# OfflineFlyback_V1.net
KiCad netlist of a schematic drawn in Altium Designer
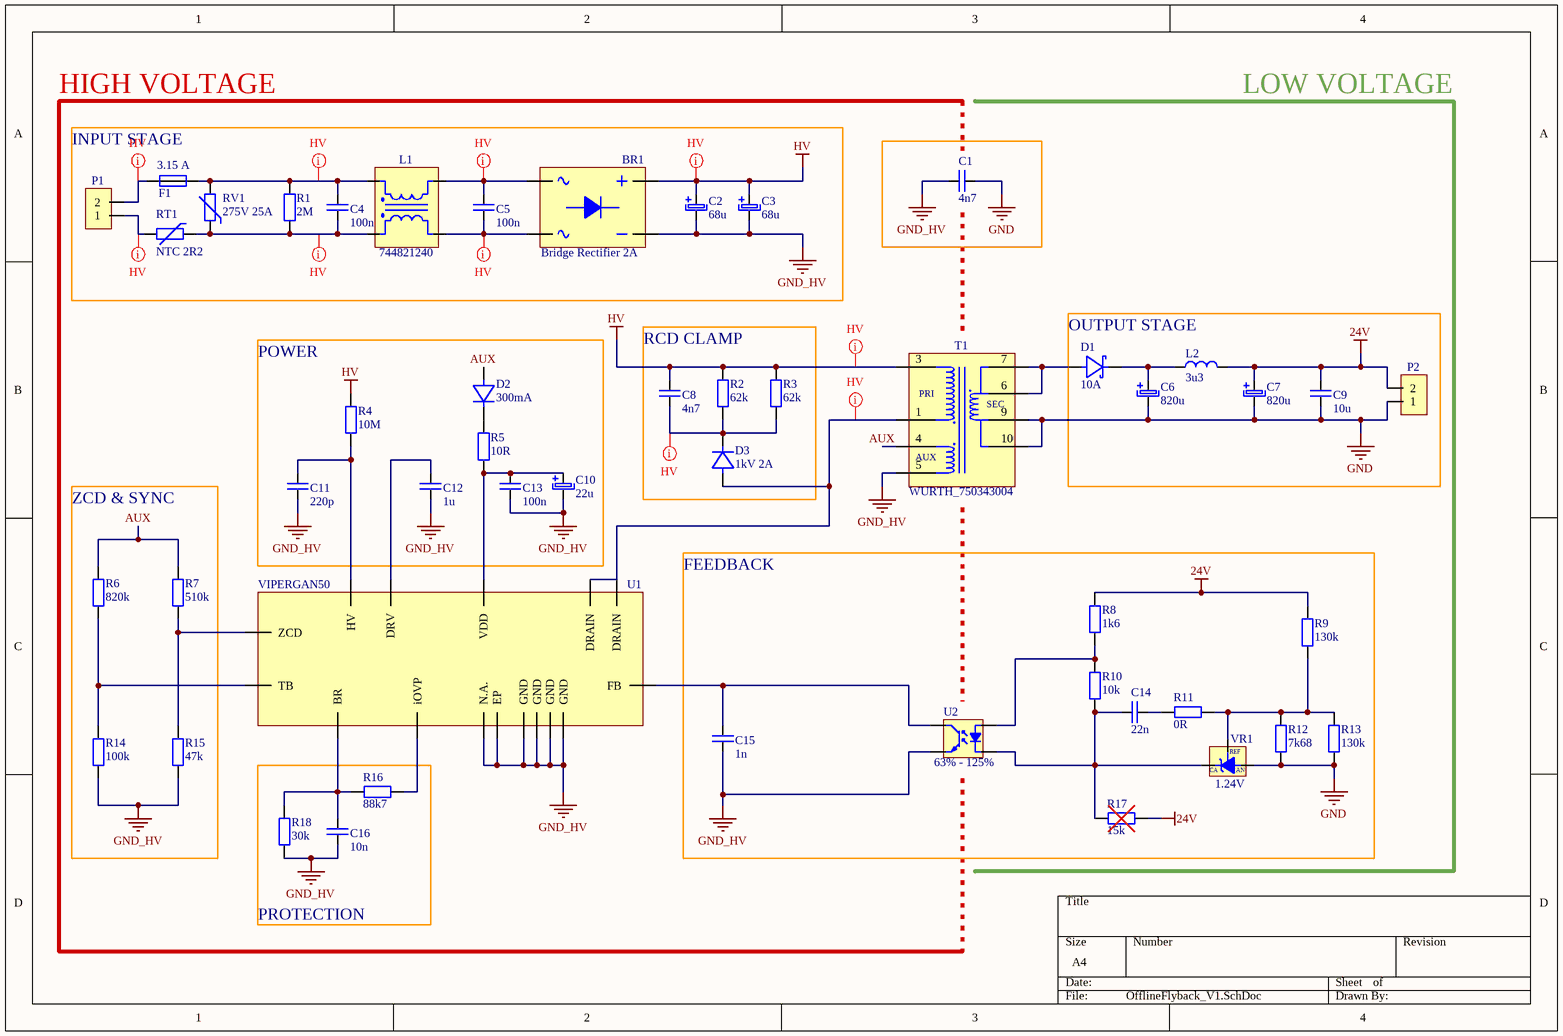
[diagram p0: OfflineFlyback_V1.SchDoc]

(export (version "E")
  (design (tool "Eeschema 10.0.6"))
  (components
    (comp (ref "BR1")
      (value "Bridge Rectifier 2A")
      (footprint "full_bridge_rectifier_SMD")
      (description "Bourns CD-MBL210SL")
      (libsource (lib "generic") (part "Bridge Rectifier"))
    )
    (comp (ref "C1")
      (value "4n7")
      (footprint "capacitor_tht_10mm_lead_2_slim")
      (description "TDK CD12ZU2GA472MYNKA Y1")
      (libsource (lib "generic") (part "Capacitor - non-polarised"))
    )
    (comp (ref "C2")
      (value "68u")
      (footprint "capacitor_tht_7mm5_lead_18mm")
      (description "Panasonic EEU-EE2G680")
      (libsource (lib "generic") (part "Capacitor - polarised"))
    )
    (comp (ref "C3")
      (value "68u")
      (footprint "capacitor_tht_7mm5_lead_18mm")
      (description "Panasonic EEU-EE2G680")
      (libsource (lib "generic") (part "Capacitor - polarised"))
    )
    (comp (ref "C4")
      (value "100n")
      (footprint "capacitor_tht_10mm_lead")
      (description "Vishay / BC Components BFC233920104 X2")
      (libsource (lib "generic") (part "Capacitor - non-polarised"))
    )
    (comp (ref "C5")
      (value "100n")
      (footprint "capacitor_tht_10mm_lead")
      (description "Vishay / BC Components BFC233920104 X2")
      (libsource (lib "generic") (part "Capacitor - non-polarised"))
    )
    (comp (ref "C6")
      (value "820u")
      (footprint "capacitor_tht_5mm_lead_10mm")
      (description "Panasonic EEU-FR1V821L")
      (libsource (lib "generic") (part "Capacitor - polarised"))
    )
    (comp (ref "C7")
      (value "820u")
      (footprint "capacitor_tht_5mm_lead_10mm")
      (description "Panasonic EEU-FR1V821L")
      (libsource (lib "generic") (part "Capacitor - polarised"))
    )
    (comp (ref "C8")
      (value "4n7")
      (footprint "capacitor_smd_1206")
      (description "Kyocera AVX 1206AC472KAT2A X7R")
      (libsource (lib "generic") (part "Capacitor - non-polarised"))
    )
    (comp (ref "C9")
      (value "10u")
      (footprint "capacitor_smd_1206")
      (description "Samsung CL31B106KBHNNNE X7R")
      (libsource (lib "generic") (part "Capacitor - non-polarised"))
    )
    (comp (ref "C10")
      (value "22u")
      (footprint "capacitor_tht_2mm5_lead_6mm3")
      (description "Wurth 860240673003")
      (libsource (lib "generic") (part "Capacitor - polarised"))
    )
    (comp (ref "C11")
      (value "220p")
      (footprint "capacitor_smd_0603")
      (description "Samsung CL10B221KC8WPNC X7R")
      (libsource (lib "generic") (part "Capacitor - non-polarised"))
    )
    (comp (ref "C12")
      (value "1u")
      (footprint "capacitor_smd_0603")
      (description "Samsung CL10B105KB9VPJC X7R")
      (libsource (lib "generic") (part "Capacitor - non-polarised"))
    )
    (comp (ref "C13")
      (value "100n")
      (footprint "capacitor_smd_0603")
      (description "Vishay / Vitramon GA0603Y104KXAAC31G X7R")
      (libsource (lib "generic") (part "Capacitor - non-polarised"))
    )
    (comp (ref "C14")
      (value "22n")
      (footprint "capacitor_smd_0603")
      (description "Kyocera AVX 06035C223K4T2A X7R")
      (libsource (lib "generic") (part "Capacitor - non-polarised"))
    )
    (comp (ref "C15")
      (value "1n")
      (footprint "capacitor_smd_0603")
      (description "Murata GRM1885C1H102JA01D C0G")
      (libsource (lib "generic") (part "Capacitor - non-polarised"))
    )
    (comp (ref "C16")
      (value "10n")
      (footprint "capacitor_smd_0603")
      (description "Murata GCM188R71H103KA37J X7R")
      (libsource (lib "generic") (part "Capacitor - non-polarised"))
    )
    (comp (ref "D1")
      (value "10A")
      (footprint "diode_TO_2787C")
      (description "Panjit MBR10H150PC-AU_R2_007A1")
      (libsource (lib "generic") (part "Diode - Schottkey"))
    )
    (comp (ref "D2")
      (value "300mA")
      (footprint "diode_smd_sod_123")
      (description "Vishay 1N4148W-HG3_A-08")
      (libsource (lib "generic") (part "Diode - silicon"))
    )
    (comp (ref "D3")
      (value "1kV 2A")
      (footprint "diode_smd_smb")
      (description "MCC FR2M-LTP")
      (libsource (lib "generic") (part "Diode - silicon"))
    )
    (comp (ref "F1")
      (value "3.15 A")
      (footprint "fuse_tht_5mm08")
      (description "Littelfuse 40013150440 3.15 A Slow Blow")
      (libsource (lib "generic") (part "Fuse"))
    )
    (comp (ref "L1")
      (value "744821240")
      (footprint "wurth_common_mode_choke_4mm5_10mm")
      (description "Wurth 744821240 1.5A 4mH")
      (libsource (lib "generic") (part "Common Mode Choke"))
    )
    (comp (ref "L2")
      (value "3u3")
      (footprint "inductor_smd_6mm6_x_7mm3")
      (description "Bourns SRP7028A-3R3M")
      (libsource (lib "generic") (part "Inductor"))
    )
    (comp (ref "P1")
      (value "Terminal Block")
      (footprint "terminal_block_1X2_5mm08")
      (description "Adam Tech EBAFA-02-D")
      (libsource (lib "") (part "Terminal Block 1X2_1"))
    )
    (comp (ref "P2")
      (value "Terminal Block")
      (footprint "terminal_block_1X2_5mm08")
      (description "Adam Tech EBAFA-02-D")
      (libsource (lib "terminal_blocks") (part "Terminal Block 1X2"))
    )
    (comp (ref "R1")
      (value "2M")
      (footprint "resisitor_smd_1206")
      (description "Vishay / Draloric RCV12062M00JNEA")
      (libsource (lib "generic") (part "Resistor"))
    )
    (comp (ref "R2")
      (value "62k")
      (footprint "resisitor_smd_1206")
      (description "Panasonic ERJ-UP8F6202V")
      (libsource (lib "generic") (part "Resistor"))
    )
    (comp (ref "R3")
      (value "62k")
      (footprint "resisitor_smd_1206")
      (description "Panasonic ERJ-UP8F6202V")
      (libsource (lib "generic") (part "Resistor"))
    )
    (comp (ref "R4")
      (value "10M")
      (footprint "resisitor_smd_1210")
      (description "ROHM KTR25JZPF1005")
      (libsource (lib "generic") (part "Resistor"))
    )
    (comp (ref "R5")
      (value "10R")
      (footprint "resisitor_smd_0603")
      (description "Vishay CRCW060310R0FKED")
      (libsource (lib "generic") (part "Resistor"))
    )
    (comp (ref "R6")
      (value "820k")
      (footprint "resisitor_smd_0603")
      (description "Walsin MR06X8203FTL")
      (libsource (lib "generic") (part "Resistor"))
    )
    (comp (ref "R7")
      (value "510k")
      (footprint "resisitor_smd_0603")
      (description "Bourns CR0603-FX-5103ELF")
      (libsource (lib "generic") (part "Resistor"))
    )
    (comp (ref "R8")
      (value "1k6")
      (footprint "resisitor_smd_0603")
      (description "Bourns CR0603-FX-1601ELF")
      (libsource (lib "generic") (part "Resistor"))
    )
    (comp (ref "R9")
      (value "130k")
      (footprint "resisitor_smd_0603")
      (description "Panasonic ERJ-3RED1303V 0.5%")
      (libsource (lib "generic") (part "Resistor"))
    )
    (comp (ref "R10")
      (value "10k")
      (footprint "resisitor_smd_0603")
      (description "Vishay / Dale CRCW060310K0FKEI")
      (libsource (lib "generic") (part "Resistor"))
    )
    (comp (ref "R11")
      (value "0R")
      (footprint "resisitor_smd_0603")
      (description "Royalohm CQ03WAF0000T5E")
      (libsource (lib "generic") (part "Resistor"))
    )
    (comp (ref "R12")
      (value "7k68")
      (footprint "resisitor_smd_0603")
      (description "Panasonic ERA-3AEB7681V 0.1%")
      (libsource (lib "generic") (part "Resistor"))
    )
    (comp (ref "R13")
      (value "130k")
      (footprint "resisitor_smd_0603")
      (description "Panasonic ERJ-3RED1303V 0.5%")
      (libsource (lib "generic") (part "Resistor"))
    )
    (comp (ref "R14")
      (value "100k")
      (footprint "resisitor_smd_0603")
      (description "Yageo AC0603FR-7W100KL")
      (libsource (lib "generic") (part "Resistor"))
    )
    (comp (ref "R15")
      (value "47k")
      (footprint "resisitor_smd_0603")
      (description "Bourns CR0603-FX-4702ELF")
      (libsource (lib "generic") (part "Resistor"))
    )
    (comp (ref "R16")
      (value "88k7")
      (footprint "resisitor_smd_0603")
      (description "Walsin WR06X8872FTL")
      (libsource (lib "generic") (part "Resistor"))
    )
    (comp (ref "R17")
      (value "15k")
      (footprint "resisitor_smd_0603")
      (description "DO NOT PLACE")
      (libsource (lib "") (part "Resistor_1"))
    )
    (comp (ref "R18")
      (value "30k")
      (footprint "resisitor_smd_0603")
      (description "Wurth 560112116107")
      (libsource (lib "generic") (part "Resistor"))
    )
    (comp (ref "RT1")
      (value "NTC 2R2")
      (footprint "thermistor_tht_7mm5")
      (description "Epcos / TDK B57237S0229M000")
      (libsource (lib "generic") (part "Thermistor"))
    )
    (comp (ref "RV1")
      (value "275V 25A")
      (footprint "varistor_tht_7mm5")
      (description "Epcos / TDK B72210S0271K101")
      (libsource (lib "generic") (part "Varistor"))
    )
    (comp (ref "T1")
      (value "WURTH_750343004")
      (footprint "WURTH_10_PIN_750343004")
      (libsource (lib "transformers") (part "Wurth - 10 pins - 750343004"))
    )
    (comp (ref "U1")
      (value "VIPERGAN50")
      (footprint "VIPERGAN50TR_V2")
      (libsource (lib "integrated_circuits") (part "VIPERGAN50 V3"))
    )
    (comp (ref "U2")
      (value "63% - 125%")
      (footprint "SMD-4")
      (description "Vishay VO615C-2X019T")
      (libsource (lib "generic") (part "Optocoupler"))
    )
    (comp (ref "VR1")
      (value "1.24V")
      (footprint "generic_sot23-3L")
      (description "STM TS3431AILT")
      (libsource (lib "integrated_circuits") (part "Programmable Shunt Voltage Reference"))
    )
  )
  (nets
    (net (code "1") (name "/AUX") (class "Default")
      (node (ref "D2") (pin "1") (pintype "passive"))
      (node (ref "R6") (pin "1") (pintype "passive"))
      (node (ref "R7") (pin "1") (pintype "passive"))
      (node (ref "T1") (pin "4") (pintype "passive"))
    )
    (net (code "2") (name "24V") (class "Default")
      (node (ref "C7") (pin "1") (pintype "passive"))
      (node (ref "C9") (pin "1") (pintype "passive"))
      (node (ref "L2") (pin "2") (pintype "passive"))
      (node (ref "P2") (pin "2") (pinfunction "2_2") (pintype "passive"))
      (node (ref "R17") (pin "2") (pintype "passive"))
      (node (ref "R8") (pin "1") (pintype "passive"))
      (node (ref "R9") (pin "1") (pintype "passive"))
    )
    (net (code "3") (name "GND") (class "Default")
      (node (ref "C1") (pin "2") (pintype "passive"))
      (node (ref "C6") (pin "2") (pintype "passive"))
      (node (ref "C7") (pin "2") (pintype "passive"))
      (node (ref "C9") (pin "2") (pintype "passive"))
      (node (ref "P2") (pin "1") (pinfunction "1_1") (pintype "passive"))
      (node (ref "R12") (pin "2") (pintype "passive"))
      (node (ref "R13") (pin "2") (pintype "passive"))
      (node (ref "T1") (pin "10") (pintype "passive"))
      (node (ref "T1") (pin "9") (pintype "passive"))
      (node (ref "VR1") (pin "3") (pintype "passive"))
    )
    (net (code "4") (name "GND_HV") (class "Default")
      (node (ref "BR1") (pin "4") (pintype "passive"))
      (node (ref "C1") (pin "1") (pintype "passive"))
      (node (ref "C10") (pin "2") (pintype "passive"))
      (node (ref "C11") (pin "2") (pintype "passive"))
      (node (ref "C12") (pin "2") (pintype "passive"))
      (node (ref "C13") (pin "2") (pintype "passive"))
      (node (ref "C15") (pin "2") (pintype "passive"))
      (node (ref "C16") (pin "2") (pintype "passive"))
      (node (ref "C2") (pin "2") (pintype "passive"))
      (node (ref "C3") (pin "2") (pintype "passive"))
      (node (ref "R14") (pin "2") (pintype "passive"))
      (node (ref "R15") (pin "2") (pintype "passive"))
      (node (ref "R18") (pin "2") (pintype "passive"))
      (node (ref "T1") (pin "5") (pintype "passive"))
      (node (ref "U1") (pin "1") (pinfunction "GND_1") (pintype "passive"))
      (node (ref "U1") (pin "2") (pinfunction "GND_2") (pintype "passive"))
      (node (ref "U1") (pin "3") (pinfunction "GND_3") (pintype "passive"))
      (node (ref "U1") (pin "4") (pinfunction "GND_4") (pintype "passive"))
      (node (ref "U1") (pin "7") (pinfunction "N.A._7") (pintype "passive"))
      (node (ref "U1") (pin "EP") (pinfunction "EP_EP") (pintype "passive"))
      (node (ref "U2") (pin "3") (pintype "passive"))
    )
    (net (code "5") (name "HV") (class "Default")
      (node (ref "BR1") (pin "3") (pintype "passive"))
      (node (ref "C2") (pin "1") (pintype "passive"))
      (node (ref "C3") (pin "1") (pintype "passive"))
      (node (ref "C8") (pin "1") (pintype "passive"))
      (node (ref "R2") (pin "1") (pintype "passive"))
      (node (ref "R3") (pin "1") (pintype "passive"))
      (node (ref "R4") (pin "1") (pintype "passive"))
      (node (ref "T1") (pin "3") (pintype "passive"))
    )
    (net (code "6") (name "Net-(BR1-Pad1)") (class "Default")
      (node (ref "BR1") (pin "1") (pintype "passive"))
      (node (ref "C5") (pin "2") (pintype "passive"))
      (node (ref "L1") (pin "3") (pintype "passive"))
    )
    (net (code "7") (name "Net-(BR1-Pad2)") (class "Default")
      (node (ref "BR1") (pin "2") (pintype "passive"))
      (node (ref "C5") (pin "1") (pintype "passive"))
      (node (ref "L1") (pin "4") (pintype "passive"))
    )
    (net (code "8") (name "Net-(C4-Pad1)") (class "Default")
      (node (ref "C4") (pin "1") (pintype "passive"))
      (node (ref "F1") (pin "2") (pintype "passive"))
      (node (ref "L1") (pin "1") (pintype "passive"))
      (node (ref "R1") (pin "1") (pintype "passive"))
      (node (ref "RV1") (pin "1") (pintype "passive"))
    )
    (net (code "9") (name "Net-(C4-Pad2)") (class "Default")
      (node (ref "C4") (pin "2") (pintype "passive"))
      (node (ref "L1") (pin "2") (pintype "passive"))
      (node (ref "R1") (pin "2") (pintype "passive"))
      (node (ref "RT1") (pin "2") (pintype "passive"))
      (node (ref "RV1") (pin "2") (pintype "passive"))
    )
    (net (code "10") (name "Net-(C6-Pad1)") (class "Default")
      (node (ref "C6") (pin "1") (pintype "passive"))
      (node (ref "D1") (pin "2") (pintype "passive"))
      (node (ref "L2") (pin "1") (pintype "passive"))
    )
    (net (code "11") (name "Net-(C8-Pad2)") (class "Default")
      (node (ref "C8") (pin "2") (pintype "passive"))
      (node (ref "D3") (pin "2") (pintype "passive"))
      (node (ref "R2") (pin "2") (pintype "passive"))
      (node (ref "R3") (pin "2") (pintype "passive"))
    )
    (net (code "12") (name "Net-(C14-Pad1)") (class "Default")
      (node (ref "C14") (pin "1") (pintype "passive"))
      (node (ref "R10") (pin "2") (pintype "passive"))
      (node (ref "R17") (pin "1") (pintype "passive"))
      (node (ref "U2") (pin "2") (pintype "passive"))
      (node (ref "VR1") (pin "2") (pintype "passive"))
    )
    (net (code "13") (name "Net-(C14-Pad2)") (class "Default")
      (node (ref "C14") (pin "2") (pintype "passive"))
      (node (ref "R11") (pin "1") (pintype "passive"))
    )
    (net (code "14") (name "Net-(D1-Pad1)") (class "Default")
      (node (ref "D1") (pin "1") (pintype "passive"))
      (node (ref "T1") (pin "6") (pintype "passive"))
      (node (ref "T1") (pin "7") (pintype "passive"))
    )
    (net (code "15") (name "Net-(D2-Pad2)") (class "Default")
      (node (ref "D2") (pin "2") (pintype "passive"))
      (node (ref "R5") (pin "1") (pintype "passive"))
    )
    (net (code "16") (name "Net-(D3-Pad1)") (class "Default")
      (node (ref "D3") (pin "1") (pintype "passive"))
      (node (ref "T1") (pin "1") (pintype "passive"))
      (node (ref "U1") (pin "15") (pinfunction "DRAIN_15") (pintype "passive"))
      (node (ref "U1") (pin "16") (pinfunction "DRAIN_16") (pintype "passive"))
    )
    (net (code "17") (name "Net-(F1-Pad1)") (class "Default")
      (node (ref "F1") (pin "1") (pintype "passive"))
      (node (ref "P1") (pin "2") (pinfunction "2_2") (pintype "passive"))
    )
    (net (code "18") (name "Net-(P1-Pad1)") (class "Default")
      (node (ref "P1") (pin "1") (pinfunction "1_1") (pintype "passive"))
      (node (ref "RT1") (pin "1") (pintype "passive"))
    )
    (net (code "19") (name "Net-(R10-Pad1)") (class "Default")
      (node (ref "R10") (pin "1") (pintype "passive"))
      (node (ref "R8") (pin "2") (pintype "passive"))
      (node (ref "U2") (pin "1") (pintype "passive"))
    )
    (net (code "20") (name "Net-(R11-Pad2)") (class "Default")
      (node (ref "R11") (pin "2") (pintype "passive"))
      (node (ref "R12") (pin "1") (pintype "passive"))
      (node (ref "R13") (pin "1") (pintype "passive"))
      (node (ref "R9") (pin "2") (pintype "passive"))
      (node (ref "VR1") (pin "1") (pintype "passive"))
    )
    (net (code "21") (name "Net-(U1-BR)") (class "Default")
      (node (ref "C16") (pin "1") (pintype "passive"))
      (node (ref "R16") (pin "1") (pintype "passive"))
      (node (ref "R18") (pin "1") (pintype "passive"))
      (node (ref "U1") (pin "5") (pinfunction "BR_5") (pintype "passive"))
    )
    (net (code "22") (name "Net-(U1-DRV)") (class "Default")
      (node (ref "C12") (pin "1") (pintype "passive"))
      (node (ref "U1") (pin "13") (pinfunction "DRV_13") (pintype "passive"))
    )
    (net (code "23") (name "Net-(U1-FB)") (class "Default")
      (node (ref "C15") (pin "1") (pintype "passive"))
      (node (ref "U1") (pin "10") (pinfunction "FB_10") (pintype "passive"))
      (node (ref "U2") (pin "4") (pintype "passive"))
    )
    (net (code "24") (name "Net-(U1-HV)") (class "Default")
      (node (ref "C11") (pin "1") (pintype "passive"))
      (node (ref "R4") (pin "2") (pintype "passive"))
      (node (ref "U1") (pin "8") (pinfunction "HV_8") (pintype "passive"))
    )
    (net (code "25") (name "Net-(U1-TB)") (class "Default")
      (node (ref "R14") (pin "1") (pintype "passive"))
      (node (ref "R6") (pin "2") (pintype "passive"))
      (node (ref "U1") (pin "9") (pinfunction "TB_9") (pintype "passive"))
    )
    (net (code "26") (name "Net-(U1-VDD)") (class "Default")
      (node (ref "C10") (pin "1") (pintype "passive"))
      (node (ref "C13") (pin "1") (pintype "passive"))
      (node (ref "R5") (pin "2") (pintype "passive"))
      (node (ref "U1") (pin "12") (pinfunction "VDD_12") (pintype "passive"))
    )
    (net (code "27") (name "Net-(U1-ZCD)") (class "Default")
      (node (ref "R15") (pin "1") (pintype "passive"))
      (node (ref "R7") (pin "2") (pintype "passive"))
      (node (ref "U1") (pin "11") (pinfunction "ZCD_11") (pintype "passive"))
    )
    (net (code "28") (name "Net-(U1-iOVP)") (class "Default")
      (node (ref "R16") (pin "2") (pintype "passive"))
      (node (ref "U1") (pin "6") (pinfunction "iOVP_6") (pintype "passive"))
    )
  )
)
